# Motors.net
KiCad netlist of a schematic drawn in Altium Designer
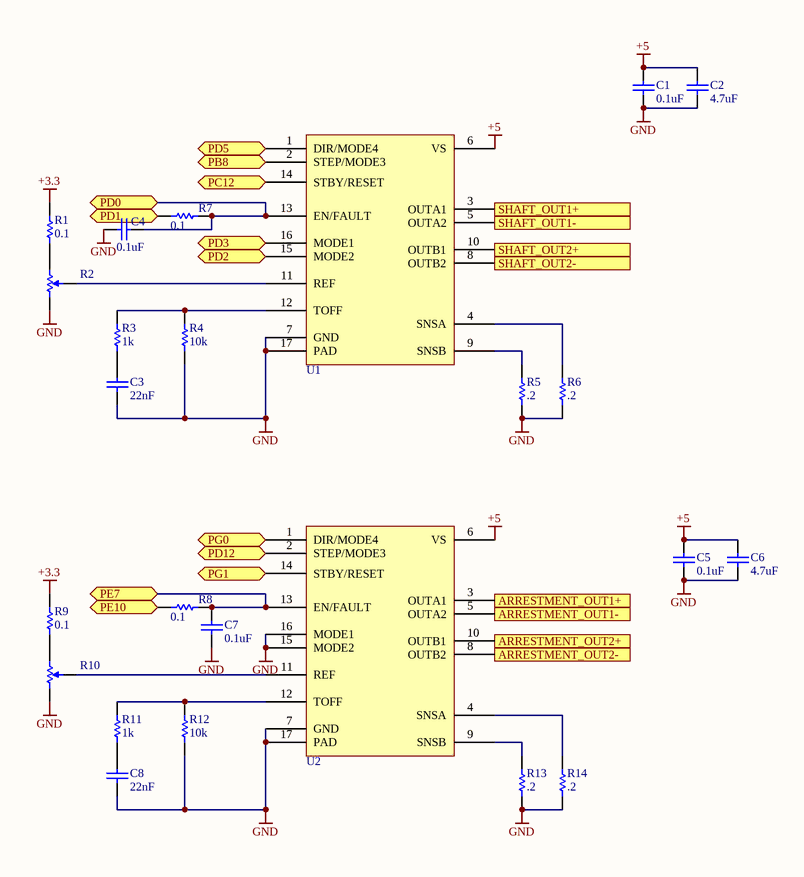
[diagram p0: Motors.SchDoc]

(export (version "E")
  (design (tool "Eeschema 10.0.6"))
  (components
    (comp (ref "C1")
      (value "0.1uF")
      (footprint "CAPC1608X94X35LL15T15")
      (description "CAP .1UF 16V CERAMIC X7R 0603")
      (fields
        (field (name "MANUFACTURER") "Yageo")
        (field (name "MANUFACTURER PART NUMBER") "CC0603KRX7R7BB105")
      )
      (libsource (lib "Altium Content Vault") (part "CAP-NP-2"))
    )
    (comp (ref "C2")
      (value "4.7uF")
      (footprint "CAPC0603(1608)55_M")
      (description "CAP 4.7uF 6.3V ±10% 0603 (1608 Metric) Thickness 0.55mm SMD")
      (fields (field (name "TOLERANCE") "Â±10%") (field (name "MANUFACTURER") "KEMET"))
      (libsource (lib "Altium Content Vault") (part "CAP"))
    )
    (comp (ref "C3")
      (value "22nF")
      (footprint "CAPC1608X94X35LL15T15")
      (description "CAP .1UF 16V CERAMIC X7R 0603")
      (fields
        (field (name "MANUFACTURER") "Yageo")
        (field (name "MANUFACTURER PART NUMBER") "CC0603KRX7R7BB105")
      )
      (libsource (lib "Altium Content Vault") (part "CMP-1661-00001-2"))
    )
    (comp (ref "C4")
      (value "0.1uF")
      (footprint "CAPC1608X94X35LL15T15")
      (description "CAP .1UF 16V CERAMIC X7R 0603")
      (fields
        (field (name "MANUFACTURER") "Yageo")
        (field (name "MANUFACTURER PART NUMBER") "CC0603KRX7R7BB105")
      )
      (libsource (lib "Altium Content Vault") (part "CAP-NP-2"))
    )
    (comp (ref "C5")
      (value "0.1uF")
      (footprint "CAPC1608X94X35LL15T15")
      (description "CAP .1UF 16V CERAMIC X7R 0603")
      (fields
        (field (name "MANUFACTURER") "Yageo")
        (field (name "MANUFACTURER PART NUMBER") "CC0603KRX7R7BB105")
      )
      (libsource (lib "Altium Content Vault") (part "CAP-NP-2"))
    )
    (comp (ref "C6")
      (value "4.7uF")
      (footprint "CAPC0603(1608)55_M")
      (description "CAP 4.7uF 6.3V ±10% 0603 (1608 Metric) Thickness 0.55mm SMD")
      (fields (field (name "TOLERANCE") "Â±10%") (field (name "MANUFACTURER") "KEMET"))
      (libsource (lib "Altium Content Vault") (part "CAP"))
    )
    (comp (ref "C7")
      (value "0.1uF")
      (footprint "CAPC1608X94X35LL15T15")
      (description "CAP .1UF 16V CERAMIC X7R 0603")
      (fields
        (field (name "MANUFACTURER") "Yageo")
        (field (name "MANUFACTURER PART NUMBER") "CC0603KRX7R7BB105")
      )
      (libsource (lib "Altium Content Vault") (part "CAP-NP-2"))
    )
    (comp (ref "C8")
      (value "22nF")
      (footprint "CAPC1608X94X35LL15T15")
      (description "CAP .1UF 16V CERAMIC X7R 0603")
      (fields
        (field (name "MANUFACTURER") "Yageo")
        (field (name "MANUFACTURER PART NUMBER") "CC0603KRX7R7BB105")
      )
      (libsource (lib "Altium Content Vault") (part "CMP-1661-00001-2"))
    )
    (comp (ref "R1")
      (value "0.1")
      (footprint "RESC0603(1608)_N")
      (description "0R12 0.1W 1% 0603 (1608 Metric)  SMD")
      (fields (field (name "POWER") "0.1 W") (field (name "TOLERANCE") "1 %"))
      (libsource (lib "Altium Content Vault") (part "RES"))
    )
    (comp (ref "R2")
      (value "3313J-1-503E")
      (footprint "BOUR-3313J-1_V")
      (fields (field (name "MANUFACTURER") "Bourns"))
      (libsource (lib "Altium Content Vault") (part "CMP-2000-05588-1"))
    )
    (comp (ref "R3")
      (value "1k")
      (footprint "RESC0603(1608)_N")
      (description "0R12 0.1W 1% 0603 (1608 Metric)  SMD")
      (fields (field (name "POWER") "0.1 W") (field (name "TOLERANCE") "1 %"))
      (libsource (lib "Altium Content Vault") (part "RES"))
    )
    (comp (ref "R4")
      (value "10k")
      (footprint "RESC0603(1608)_N")
      (description "0R12 0.1W 1% 0603 (1608 Metric)  SMD")
      (fields (field (name "POWER") "0.1 W") (field (name "TOLERANCE") "1 %"))
      (libsource (lib "Altium Content Vault") (part "RES"))
    )
    (comp (ref "R5")
      (value ".2")
      (footprint "RESC0603(1608)_N")
      (description "0R12 0.1W 1% 0603 (1608 Metric)  SMD")
      (fields (field (name "POWER") "0.1 W") (field (name "TOLERANCE") "1 %"))
      (libsource (lib "Altium Content Vault") (part "CMP-1012-00511-1"))
    )
    (comp (ref "R6")
      (value ".2")
      (footprint "RESC0603(1608)_N")
      (description "0R12 0.1W 1% 0603 (1608 Metric)  SMD")
      (fields (field (name "POWER") "0.1 W") (field (name "TOLERANCE") "1 %"))
      (libsource (lib "Altium Content Vault") (part "RES"))
    )
    (comp (ref "R7")
      (value "0.1")
      (footprint "RESC0603(1608)_N")
      (description "0R12 0.1W 1% 0603 (1608 Metric)  SMD")
      (fields (field (name "POWER") "0.1 W") (field (name "TOLERANCE") "1 %"))
      (libsource (lib "Altium Content Vault") (part "RES"))
    )
    (comp (ref "R8")
      (value "0.1")
      (footprint "RESC0603(1608)_N")
      (description "0R12 0.1W 1% 0603 (1608 Metric)  SMD")
      (fields (field (name "POWER") "0.1 W") (field (name "TOLERANCE") "1 %"))
      (libsource (lib "Altium Content Vault") (part "RES"))
    )
    (comp (ref "R9")
      (value "0.1")
      (footprint "RESC0603(1608)_N")
      (description "0R12 0.1W 1% 0603 (1608 Metric)  SMD")
      (fields (field (name "POWER") "0.1 W") (field (name "TOLERANCE") "1 %"))
      (libsource (lib "Altium Content Vault") (part "RES"))
    )
    (comp (ref "R10")
      (value "3313J-1-503E")
      (footprint "BOUR-3313J-1_V")
      (fields (field (name "MANUFACTURER") "Bourns"))
      (libsource (lib "Altium Content Vault") (part "CMP-2000-05588-1"))
    )
    (comp (ref "R11")
      (value "1k")
      (footprint "RESC0603(1608)_N")
      (description "0R12 0.1W 1% 0603 (1608 Metric)  SMD")
      (fields (field (name "POWER") "0.1 W") (field (name "TOLERANCE") "1 %"))
      (libsource (lib "Altium Content Vault") (part "RES"))
    )
    (comp (ref "R12")
      (value "10k")
      (footprint "RESC0603(1608)_N")
      (description "0R12 0.1W 1% 0603 (1608 Metric)  SMD")
      (fields (field (name "POWER") "0.1 W") (field (name "TOLERANCE") "1 %"))
      (libsource (lib "Altium Content Vault") (part "RES"))
    )
    (comp (ref "R13")
      (value ".2")
      (footprint "RESC0603(1608)_N")
      (description "0R12 0.1W 1% 0603 (1608 Metric)  SMD")
      (fields (field (name "POWER") "0.1 W") (field (name "TOLERANCE") "1 %"))
      (libsource (lib "Altium Content Vault") (part "CMP-1012-00511-1"))
    )
    (comp (ref "R14")
      (value ".2")
      (footprint "RESC0603(1608)_N")
      (description "0R12 0.1W 1% 0603 (1608 Metric)  SMD")
      (fields (field (name "POWER") "0.1 W") (field (name "TOLERANCE") "1 %"))
      (libsource (lib "Altium Content Vault") (part "RES"))
    )
    (comp (ref "U1")
      (value "STSPIN220")
      (footprint "STSPIN220-QFN127P600-8N")
      (libsource (lib "ZLS_Schematic_lib") (part "STSPIN220"))
    )
    (comp (ref "U2")
      (value "STSPIN220")
      (footprint "STSPIN220-QFN127P600-8N")
      (libsource (lib "ZLS_Schematic_lib") (part "STSPIN220"))
    )
  )
  (nets
    (net (code "1") (name "+3.3") (class "Default")
      (node (ref "R1") (pin "2") (pinfunction "2_2") (pintype "passive"))
      (node (ref "R9") (pin "2") (pinfunction "2_2") (pintype "passive"))
    )
    (net (code "2") (name "+5") (class "Default")
      (node (ref "C1") (pin "1") (pinfunction "1_1") (pintype "passive"))
      (node (ref "C2") (pin "2") (pinfunction "2_2") (pintype "passive"))
      (node (ref "C5") (pin "1") (pinfunction "1_1") (pintype "passive"))
      (node (ref "C6") (pin "2") (pinfunction "2_2") (pintype "passive"))
      (node (ref "U1") (pin "6") (pinfunction "VS_6") (pintype "passive"))
      (node (ref "U2") (pin "6") (pinfunction "VS_6") (pintype "passive"))
    )
    (net (code "3") (name "/ARRESTMENT_OUT1+") (class "Default")
      (node (ref "U2") (pin "3") (pinfunction "OUTA1_3") (pintype "passive"))
    )
    (net (code "4") (name "/ARRESTMENT_OUT1-") (class "Default")
      (node (ref "U2") (pin "5") (pinfunction "OUTA2_5") (pintype "passive"))
    )
    (net (code "5") (name "/ARRESTMENT_OUT2+") (class "Default")
      (node (ref "U2") (pin "10") (pinfunction "OUTB1_10") (pintype "passive"))
    )
    (net (code "6") (name "/ARRESTMENT_OUT2-") (class "Default")
      (node (ref "U2") (pin "8") (pinfunction "OUTB2_8") (pintype "passive"))
    )
    (net (code "7") (name "/PB8") (class "Default")
      (node (ref "U1") (pin "2") (pinfunction "STEP/MODE3_2") (pintype "passive"))
    )
    (net (code "8") (name "/PC12") (class "Default")
      (node (ref "U1") (pin "14") (pinfunction "STBY/RESET_14") (pintype "passive"))
    )
    (net (code "9") (name "/PD0") (class "Default")
      (node (ref "C4") (pin "2") (pinfunction "2_2") (pintype "passive"))
      (node (ref "R7") (pin "1") (pinfunction "1_1") (pintype "passive"))
      (node (ref "U1") (pin "13") (pinfunction "EN/FAULT_13") (pintype "passive"))
    )
    (net (code "10") (name "/PD1") (class "Default")
      (node (ref "R7") (pin "2") (pinfunction "2_2") (pintype "passive"))
    )
    (net (code "11") (name "/PD2") (class "Default")
      (node (ref "U1") (pin "15") (pinfunction "MODE2_15") (pintype "passive"))
    )
    (net (code "12") (name "/PD3") (class "Default")
      (node (ref "U1") (pin "16") (pinfunction "MODE1_16") (pintype "passive"))
    )
    (net (code "13") (name "/PD5") (class "Default")
      (node (ref "U1") (pin "1") (pinfunction "DIR/MODE4_1") (pintype "passive"))
    )
    (net (code "14") (name "/PD12") (class "Default")
      (node (ref "U2") (pin "2") (pinfunction "STEP/MODE3_2") (pintype "passive"))
    )
    (net (code "15") (name "/PE7") (class "Default")
      (node (ref "C7") (pin "2") (pinfunction "2_2") (pintype "passive"))
      (node (ref "R8") (pin "1") (pinfunction "1_1") (pintype "passive"))
      (node (ref "U2") (pin "13") (pinfunction "EN/FAULT_13") (pintype "passive"))
    )
    (net (code "16") (name "/PE10") (class "Default")
      (node (ref "R8") (pin "2") (pinfunction "2_2") (pintype "passive"))
    )
    (net (code "17") (name "/PG0") (class "Default")
      (node (ref "U2") (pin "1") (pinfunction "DIR/MODE4_1") (pintype "passive"))
    )
    (net (code "18") (name "/PG1") (class "Default")
      (node (ref "U2") (pin "14") (pinfunction "STBY/RESET_14") (pintype "passive"))
    )
    (net (code "19") (name "/SHAFT_OUT1+") (class "Default")
      (node (ref "U1") (pin "3") (pinfunction "OUTA1_3") (pintype "passive"))
    )
    (net (code "20") (name "/SHAFT_OUT1-") (class "Default")
      (node (ref "U1") (pin "5") (pinfunction "OUTA2_5") (pintype "passive"))
    )
    (net (code "21") (name "/SHAFT_OUT2+") (class "Default")
      (node (ref "U1") (pin "10") (pinfunction "OUTB1_10") (pintype "passive"))
    )
    (net (code "22") (name "/SHAFT_OUT2-") (class "Default")
      (node (ref "U1") (pin "8") (pinfunction "OUTB2_8") (pintype "passive"))
    )
    (net (code "23") (name "GND") (class "Default")
      (node (ref "C1") (pin "2") (pinfunction "2_2") (pintype "passive"))
      (node (ref "C2") (pin "1") (pinfunction "1_1") (pintype "passive"))
      (node (ref "C3") (pin "2") (pinfunction "2_2") (pintype "passive"))
      (node (ref "C4") (pin "1") (pinfunction "1_1") (pintype "passive"))
      (node (ref "C5") (pin "2") (pinfunction "2_2") (pintype "passive"))
      (node (ref "C6") (pin "1") (pinfunction "1_1") (pintype "passive"))
      (node (ref "C7") (pin "1") (pinfunction "1_1") (pintype "passive"))
      (node (ref "C8") (pin "2") (pinfunction "2_2") (pintype "passive"))
      (node (ref "R10") (pin "1") (pinfunction "1_1") (pintype "passive"))
      (node (ref "R12") (pin "1") (pinfunction "1_1") (pintype "passive"))
      (node (ref "R13") (pin "1") (pinfunction "1_1") (pintype "passive"))
      (node (ref "R14") (pin "1") (pinfunction "1_1") (pintype "passive"))
      (node (ref "R2") (pin "1") (pinfunction "1_1") (pintype "passive"))
      (node (ref "R4") (pin "1") (pinfunction "1_1") (pintype "passive"))
      (node (ref "R5") (pin "1") (pinfunction "1_1") (pintype "passive"))
      (node (ref "R6") (pin "1") (pinfunction "1_1") (pintype "passive"))
      (node (ref "U1") (pin "17") (pinfunction "PAD_17") (pintype "passive"))
      (node (ref "U1") (pin "7") (pinfunction "GND_7") (pintype "passive"))
      (node (ref "U2") (pin "15") (pinfunction "MODE2_15") (pintype "passive"))
      (node (ref "U2") (pin "16") (pinfunction "MODE1_16") (pintype "passive"))
      (node (ref "U2") (pin "17") (pinfunction "PAD_17") (pintype "passive"))
      (node (ref "U2") (pin "7") (pinfunction "GND_7") (pintype "passive"))
    )
    (net (code "24") (name "Net-(C3-Pad1)") (class "Default")
      (node (ref "C3") (pin "1") (pinfunction "1_1") (pintype "passive"))
      (node (ref "R3") (pin "1") (pinfunction "1_1") (pintype "passive"))
    )
    (net (code "25") (name "Net-(C8-Pad1)") (class "Default")
      (node (ref "C8") (pin "1") (pinfunction "1_1") (pintype "passive"))
      (node (ref "R11") (pin "1") (pinfunction "1_1") (pintype "passive"))
    )
    (net (code "26") (name "Net-(R1-Pad1)") (class "Default")
      (node (ref "R1") (pin "1") (pinfunction "1_1") (pintype "passive"))
      (node (ref "R2") (pin "3") (pinfunction "3_3") (pintype "passive"))
    )
    (net (code "27") (name "Net-(R10-Pad3)") (class "Default")
      (node (ref "R10") (pin "3") (pinfunction "3_3") (pintype "passive"))
      (node (ref "R9") (pin "1") (pinfunction "1_1") (pintype "passive"))
    )
    (net (code "28") (name "Net-(U1-REF)") (class "Default")
      (node (ref "R2") (pin "2") (pinfunction "2_2") (pintype "passive"))
      (node (ref "U1") (pin "11") (pinfunction "REF_11") (pintype "passive"))
    )
    (net (code "29") (name "Net-(U1-SNSA)") (class "Default")
      (node (ref "R6") (pin "2") (pinfunction "2_2") (pintype "passive"))
      (node (ref "U1") (pin "4") (pinfunction "SNSA_4") (pintype "passive"))
    )
    (net (code "30") (name "Net-(U1-SNSB)") (class "Default")
      (node (ref "R5") (pin "2") (pinfunction "2_2") (pintype "passive"))
      (node (ref "U1") (pin "9") (pinfunction "SNSB_9") (pintype "passive"))
    )
    (net (code "31") (name "Net-(U1-TOFF)") (class "Default")
      (node (ref "R3") (pin "2") (pinfunction "2_2") (pintype "passive"))
      (node (ref "R4") (pin "2") (pinfunction "2_2") (pintype "passive"))
      (node (ref "U1") (pin "12") (pinfunction "TOFF_12") (pintype "passive"))
    )
    (net (code "32") (name "Net-(U2-REF)") (class "Default")
      (node (ref "R10") (pin "2") (pinfunction "2_2") (pintype "passive"))
      (node (ref "U2") (pin "11") (pinfunction "REF_11") (pintype "passive"))
    )
    (net (code "33") (name "Net-(U2-SNSA)") (class "Default")
      (node (ref "R14") (pin "2") (pinfunction "2_2") (pintype "passive"))
      (node (ref "U2") (pin "4") (pinfunction "SNSA_4") (pintype "passive"))
    )
    (net (code "34") (name "Net-(U2-SNSB)") (class "Default")
      (node (ref "R13") (pin "2") (pinfunction "2_2") (pintype "passive"))
      (node (ref "U2") (pin "9") (pinfunction "SNSB_9") (pintype "passive"))
    )
    (net (code "35") (name "Net-(U2-TOFF)") (class "Default")
      (node (ref "R11") (pin "2") (pinfunction "2_2") (pintype "passive"))
      (node (ref "R12") (pin "2") (pinfunction "2_2") (pintype "passive"))
      (node (ref "U2") (pin "12") (pinfunction "TOFF_12") (pintype "passive"))
    )
  )
)
